# AJH_as3310_DUAL_ASR_02_4hp.net
KiCad netlist of a schematic drawn in EAGLE
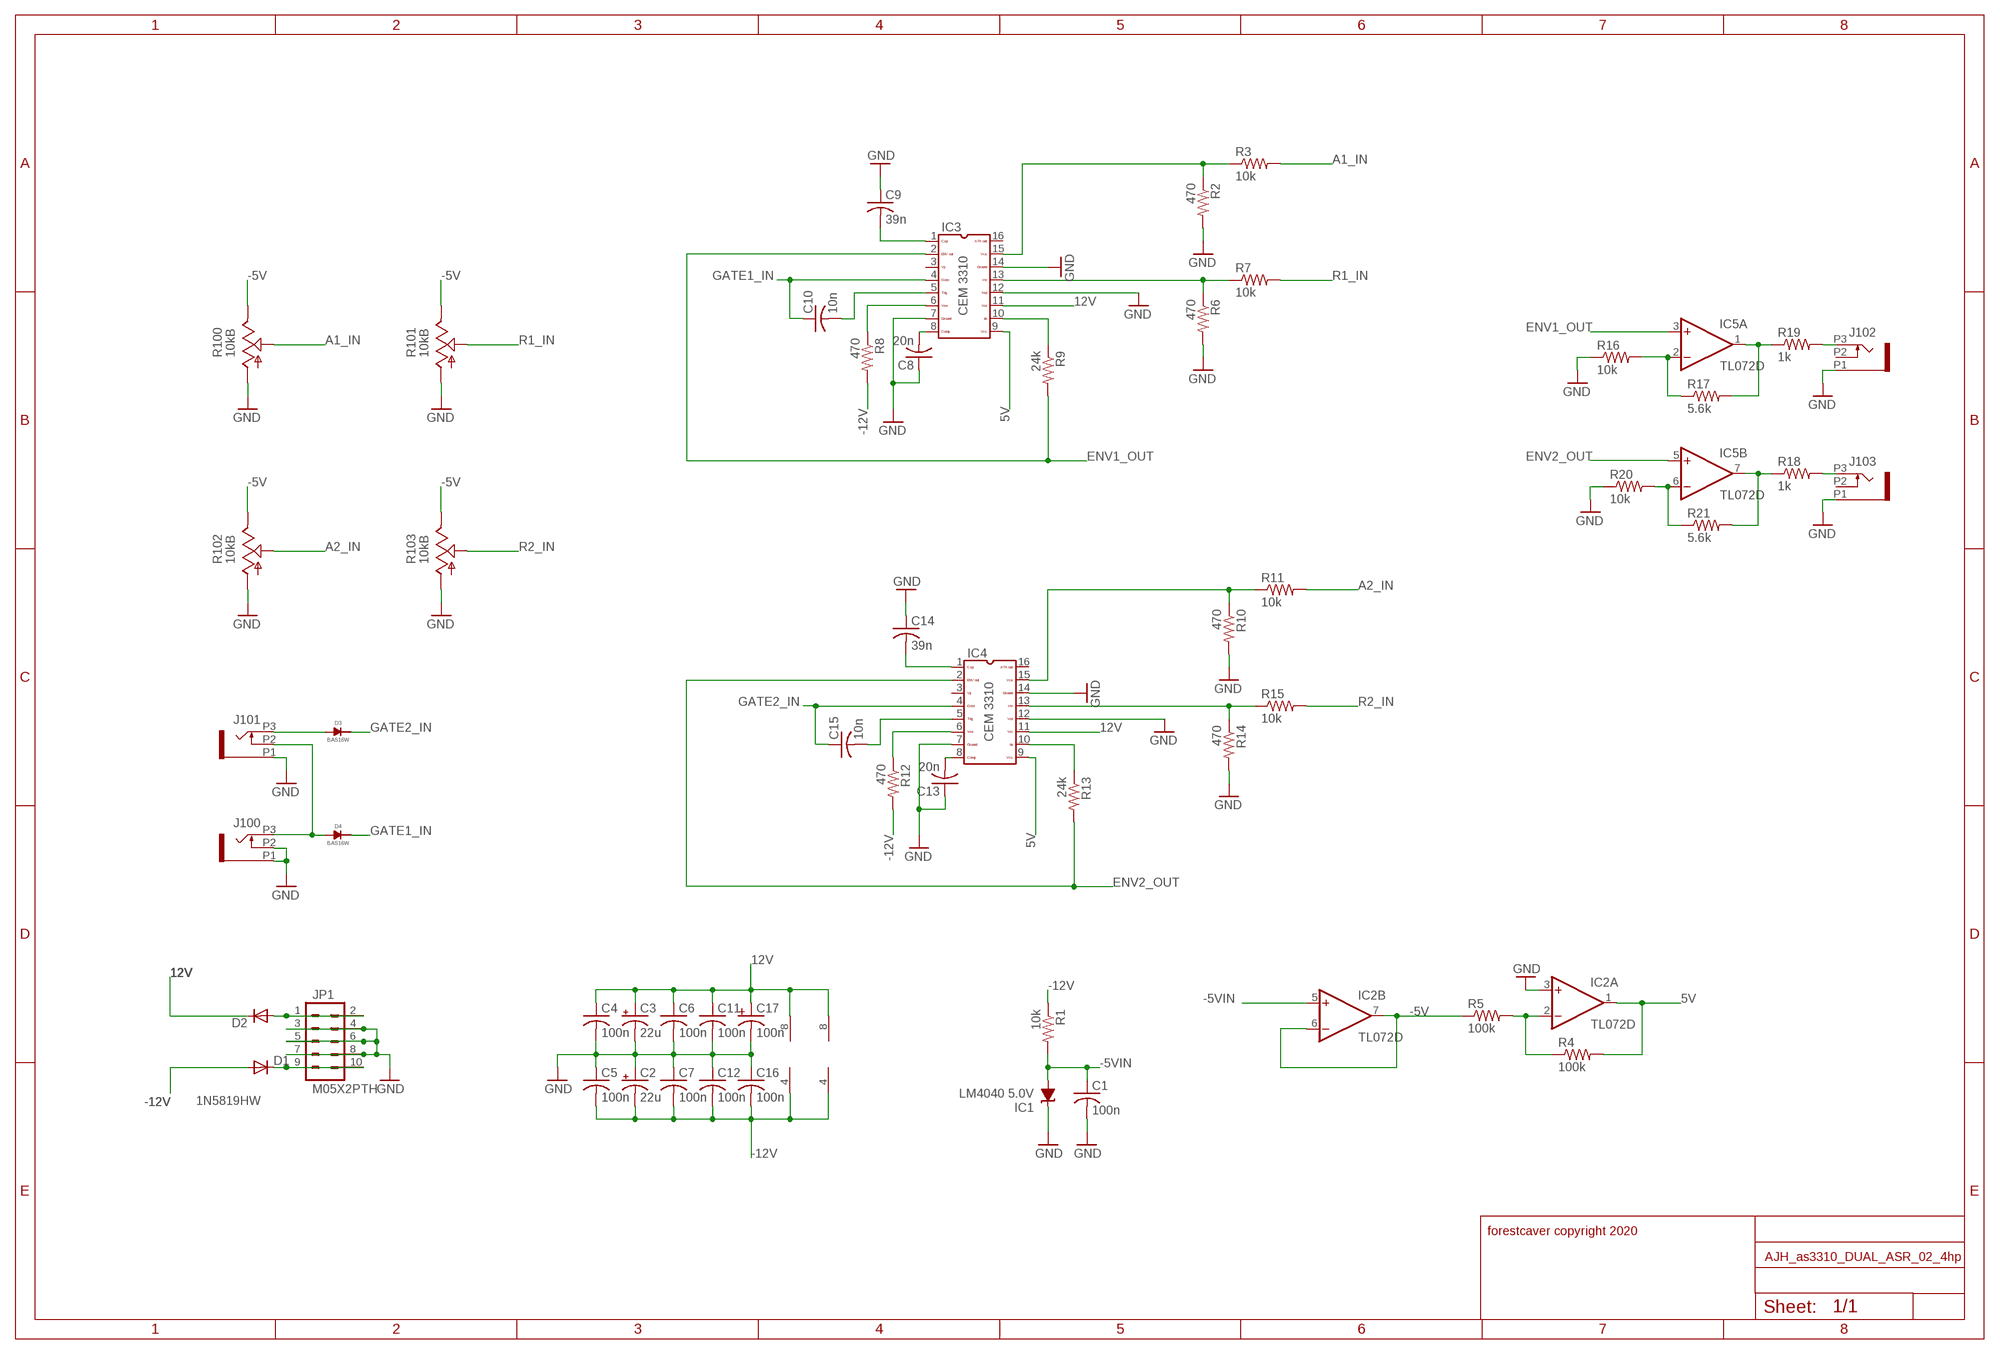
[diagram p0: schematic, sheet 1]

(export (version "E")
  (design (tool "Eeschema 10.0.6"))
  (components
    (comp (ref "C1")
      (value "100n")
      (footprint "eagle-import:C0603")
      (libsource (lib "eagle-import") (part "C-USC0603"))
    )
    (comp (ref "C2")
      (value "22u")
      (footprint "eagle-import:PANASONIC_B")
      (libsource (lib "eagle-import") (part "CPOL-USB"))
    )
    (comp (ref "C3")
      (value "22u")
      (footprint "eagle-import:PANASONIC_B")
      (libsource (lib "eagle-import") (part "CPOL-USB"))
    )
    (comp (ref "C4")
      (value "100n")
      (footprint "eagle-import:C0603")
      (libsource (lib "eagle-import") (part "C-USC0603"))
    )
    (comp (ref "C5")
      (value "100n")
      (footprint "eagle-import:C0603")
      (libsource (lib "eagle-import") (part "C-USC0603"))
    )
    (comp (ref "C6")
      (value "100n")
      (footprint "eagle-import:C0603")
      (libsource (lib "eagle-import") (part "C-USC0603"))
    )
    (comp (ref "C7")
      (value "100n")
      (footprint "eagle-import:C0603")
      (libsource (lib "eagle-import") (part "C-USC0603"))
    )
    (comp (ref "C8")
      (value "20n")
      (footprint "eagle-import:C0603")
      (libsource (lib "eagle-import") (part "C-USC0603"))
    )
    (comp (ref "C9")
      (value "39n")
      (footprint "eagle-import:C0603")
      (libsource (lib "eagle-import") (part "C-USC0603"))
    )
    (comp (ref "C10")
      (value "10n")
      (footprint "eagle-import:C0603")
      (libsource (lib "eagle-import") (part "C-USC0603"))
    )
    (comp (ref "C11")
      (value "100n")
      (footprint "eagle-import:C0603")
      (libsource (lib "eagle-import") (part "C-USC0603"))
    )
    (comp (ref "C12")
      (value "100n")
      (footprint "eagle-import:C0603")
      (libsource (lib "eagle-import") (part "C-USC0603"))
    )
    (comp (ref "C13")
      (value "20n")
      (footprint "eagle-import:C0603")
      (libsource (lib "eagle-import") (part "C-USC0603"))
    )
    (comp (ref "C14")
      (value "39n")
      (footprint "eagle-import:C0603")
      (libsource (lib "eagle-import") (part "C-USC0603"))
    )
    (comp (ref "C15")
      (value "10n")
      (footprint "eagle-import:C0603")
      (libsource (lib "eagle-import") (part "C-USC0603"))
    )
    (comp (ref "C16")
      (value "100n")
      (footprint "eagle-import:C0603")
      (libsource (lib "eagle-import") (part "C-USC0603"))
    )
    (comp (ref "C17")
      (value "100n")
      (footprint "eagle-import:C0603")
      (libsource (lib "eagle-import") (part "C-USC0603"))
    )
    (comp (ref "D1")
      (value "1N5819HW")
      (footprint "eagle-import:SOD123")
      (libsource (lib "eagle-import") (part "DIODE-SOD123"))
    )
    (comp (ref "D2")
      (value "1N5819HW")
      (footprint "eagle-import:SOD123")
      (libsource (lib "eagle-import") (part "DIODE-SOD123"))
    )
    (comp (ref "D3")
      (value "BAS16W")
      (footprint "eagle-import:SOT-323")
      (libsource (lib "eagle-import") (part "BAS16W"))
    )
    (comp (ref "D4")
      (value "BAS16W")
      (footprint "eagle-import:SOT-323")
      (libsource (lib "eagle-import") (part "BAS16W"))
    )
    (comp (ref "IC1")
      (value "LM4040 5.0V")
      (footprint "eagle-import:DBZ_R-PDSO-G3")
      (libsource (lib "eagle-import") (part "LM4041DBZC12"))
    )
    (comp (ref "IC2")
      (value "TL072D")
      (footprint "eagle-import:SO08")
      (libsource (lib "eagle-import") (part "TL072D"))
    )
    (comp (ref "IC3")
      (value "CEM3310SOIC16")
      (footprint "eagle-import:SO16")
      (libsource (lib "eagle-import") (part "CEM3310SOIC16"))
    )
    (comp (ref "IC4")
      (value "CEM3310SOIC16")
      (footprint "eagle-import:SO16")
      (libsource (lib "eagle-import") (part "CEM3310SOIC16"))
    )
    (comp (ref "IC5")
      (value "TL072D")
      (footprint "eagle-import:SO08")
      (libsource (lib "eagle-import") (part "TL072D"))
    )
    (comp (ref "J100")
      (value "PJ301_THONKICONN6")
      (footprint "eagle-import:WQP_PJ_301M6")
      (libsource (lib "eagle-import") (part "PJ301_THONKICONN6"))
    )
    (comp (ref "J101")
      (value "PJ301_THONKICONN6")
      (footprint "eagle-import:WQP_PJ_301M6")
      (libsource (lib "eagle-import") (part "PJ301_THONKICONN6"))
    )
    (comp (ref "J102")
      (value "PJ301_THONKICONN6")
      (footprint "eagle-import:WQP_PJ_301M6")
      (libsource (lib "eagle-import") (part "PJ301_THONKICONN6"))
    )
    (comp (ref "J103")
      (value "PJ301_THONKICONN6")
      (footprint "eagle-import:WQP_PJ_301M6")
      (libsource (lib "eagle-import") (part "PJ301_THONKICONN6"))
    )
    (comp (ref "JP1")
      (value "M05X2PTH")
      (footprint "eagle-import:AVR_ICSP")
      (libsource (lib "eagle-import") (part "M05X2PTH"))
    )
    (comp (ref "R1")
      (value "10k")
      (footprint "eagle-import:R0603")
      (libsource (lib "eagle-import") (part "R-US_R0603"))
    )
    (comp (ref "R2")
      (value "470")
      (footprint "eagle-import:R0603")
      (libsource (lib "eagle-import") (part "R-US_R0603"))
    )
    (comp (ref "R3")
      (value "10k")
      (footprint "eagle-import:R0603")
      (libsource (lib "eagle-import") (part "R-US_R0603"))
    )
    (comp (ref "R4")
      (value "100k")
      (footprint "eagle-import:R0603")
      (libsource (lib "eagle-import") (part "R-US_R0603"))
    )
    (comp (ref "R5")
      (value "100k")
      (footprint "eagle-import:R0603")
      (libsource (lib "eagle-import") (part "R-US_R0603"))
    )
    (comp (ref "R6")
      (value "470")
      (footprint "eagle-import:R0603")
      (libsource (lib "eagle-import") (part "R-US_R0603"))
    )
    (comp (ref "R7")
      (value "10k")
      (footprint "eagle-import:R0603")
      (libsource (lib "eagle-import") (part "R-US_R0603"))
    )
    (comp (ref "R8")
      (value "470")
      (footprint "eagle-import:R0603")
      (libsource (lib "eagle-import") (part "R-US_R0603"))
    )
    (comp (ref "R9")
      (value "24k")
      (footprint "eagle-import:R0603")
      (libsource (lib "eagle-import") (part "R-US_R0603"))
    )
    (comp (ref "R10")
      (value "470")
      (footprint "eagle-import:R0603")
      (libsource (lib "eagle-import") (part "R-US_R0603"))
    )
    (comp (ref "R11")
      (value "10k")
      (footprint "eagle-import:R0603")
      (libsource (lib "eagle-import") (part "R-US_R0603"))
    )
    (comp (ref "R12")
      (value "470")
      (footprint "eagle-import:R0603")
      (libsource (lib "eagle-import") (part "R-US_R0603"))
    )
    (comp (ref "R13")
      (value "24k")
      (footprint "eagle-import:R0603")
      (libsource (lib "eagle-import") (part "R-US_R0603"))
    )
    (comp (ref "R14")
      (value "470")
      (footprint "eagle-import:R0603")
      (libsource (lib "eagle-import") (part "R-US_R0603"))
    )
    (comp (ref "R15")
      (value "10k")
      (footprint "eagle-import:R0603")
      (libsource (lib "eagle-import") (part "R-US_R0603"))
    )
    (comp (ref "R16")
      (value "10k")
      (footprint "eagle-import:R0603")
      (libsource (lib "eagle-import") (part "R-US_R0603"))
    )
    (comp (ref "R17")
      (value "5.6k")
      (footprint "eagle-import:R0603")
      (libsource (lib "eagle-import") (part "R-US_R0603"))
    )
    (comp (ref "R18")
      (value "1k")
      (footprint "eagle-import:R0603")
      (libsource (lib "eagle-import") (part "R-US_R0603"))
    )
    (comp (ref "R19")
      (value "1k")
      (footprint "eagle-import:R0603")
      (libsource (lib "eagle-import") (part "R-US_R0603"))
    )
    (comp (ref "R20")
      (value "10k")
      (footprint "eagle-import:R0603")
      (libsource (lib "eagle-import") (part "R-US_R0603"))
    )
    (comp (ref "R21")
      (value "5.6k")
      (footprint "eagle-import:R0603")
      (libsource (lib "eagle-import") (part "R-US_R0603"))
    )
    (comp (ref "R100")
      (value "10kB")
      (footprint "eagle-import:ALPS_POT_VERTICAL")
      (libsource (lib "eagle-import") (part "POT_USVERTICAL"))
    )
    (comp (ref "R101")
      (value "10kB")
      (footprint "eagle-import:ALPS_POT_VERTICAL")
      (libsource (lib "eagle-import") (part "POT_USVERTICAL"))
    )
    (comp (ref "R102")
      (value "10kB")
      (footprint "eagle-import:ALPS_POT_VERTICAL")
      (libsource (lib "eagle-import") (part "POT_USVERTICAL"))
    )
    (comp (ref "R103")
      (value "10kB")
      (footprint "eagle-import:ALPS_POT_VERTICAL")
      (libsource (lib "eagle-import") (part "POT_USVERTICAL"))
    )
  )
  (nets
    (net (code "1") (name "/-5V") (class "Default")
      (node (ref "IC2") (pin "6") (pinfunction "-IN_6") (pintype "input"))
      (node (ref "IC2") (pin "7") (pinfunction "OUT_7") (pintype "output"))
      (node (ref "R100") (pin "P$1") (pinfunction "E_P$1") (pintype "passive"))
      (node (ref "R101") (pin "P$1") (pinfunction "E_P$1") (pintype "passive"))
      (node (ref "R102") (pin "P$1") (pinfunction "E_P$1") (pintype "passive"))
      (node (ref "R103") (pin "P$1") (pinfunction "E_P$1") (pintype "passive"))
      (node (ref "R5") (pin "1") (pinfunction "1_1") (pintype "passive"))
    )
    (net (code "2") (name "/-5VIN") (class "Default")
      (node (ref "C1") (pin "1") (pinfunction "1_1") (pintype "passive"))
      (node (ref "IC1") (pin "2") (pinfunction "A_2") (pintype "passive"))
      (node (ref "IC2") (pin "5") (pinfunction "+IN_5") (pintype "input"))
      (node (ref "R1") (pin "2") (pinfunction "2_2") (pintype "passive"))
    )
    (net (code "3") (name "/-12V") (class "Default")
      (node (ref "C12") (pin "2") (pinfunction "2_2") (pintype "passive"))
      (node (ref "C16") (pin "2") (pinfunction "2_2") (pintype "passive"))
      (node (ref "C2") (pin "-") (pinfunction "-_-") (pintype "passive"))
      (node (ref "C5") (pin "2") (pinfunction "2_2") (pintype "passive"))
      (node (ref "C7") (pin "2") (pinfunction "2_2") (pintype "passive"))
      (node (ref "D1") (pin "A") (pinfunction "A_A") (pintype "passive"))
      (node (ref "IC2") (pin "4") (pinfunction "V-_4") (pintype "power_in"))
      (node (ref "IC5") (pin "4") (pinfunction "V-_4") (pintype "power_in"))
      (node (ref "R1") (pin "1") (pinfunction "1_1") (pintype "passive"))
      (node (ref "R12") (pin "2") (pinfunction "2_2") (pintype "passive"))
      (node (ref "R8") (pin "2") (pinfunction "2_2") (pintype "passive"))
    )
    (net (code "4") (name "/5V") (class "Default")
      (node (ref "IC2") (pin "1") (pinfunction "OUT_1") (pintype "output"))
      (node (ref "IC3") (pin "9") (pinfunction "9_9") (pintype "power_in"))
      (node (ref "IC4") (pin "9") (pinfunction "9_9") (pintype "power_in"))
      (node (ref "R4") (pin "2") (pinfunction "2_2") (pintype "passive"))
    )
    (net (code "5") (name "/12V") (class "Default")
      (node (ref "C11") (pin "1") (pinfunction "1_1") (pintype "passive"))
      (node (ref "C17") (pin "1") (pinfunction "1_1") (pintype "passive"))
      (node (ref "C3") (pin "+") (pinfunction "+_+") (pintype "passive"))
      (node (ref "C4") (pin "1") (pinfunction "1_1") (pintype "passive"))
      (node (ref "C6") (pin "1") (pinfunction "1_1") (pintype "passive"))
      (node (ref "D2") (pin "C") (pinfunction "C_C") (pintype "passive"))
      (node (ref "IC2") (pin "8") (pinfunction "V+_8") (pintype "power_in"))
      (node (ref "IC3") (pin "11") (pinfunction "11_11") (pintype "power_in"))
      (node (ref "IC4") (pin "11") (pinfunction "11_11") (pintype "power_in"))
      (node (ref "IC5") (pin "8") (pinfunction "V+_8") (pintype "power_in"))
    )
    (net (code "6") (name "/A1_IN") (class "Default")
      (node (ref "R100") (pin "P$2") (pinfunction "S_P$2") (pintype "passive"))
      (node (ref "R3") (pin "2") (pinfunction "2_2") (pintype "passive"))
    )
    (net (code "7") (name "/A2_IN") (class "Default")
      (node (ref "R102") (pin "P$2") (pinfunction "S_P$2") (pintype "passive"))
      (node (ref "R11") (pin "2") (pinfunction "2_2") (pintype "passive"))
    )
    (net (code "8") (name "/ENV1_OUT") (class "Default")
      (node (ref "IC3") (pin "2") (pinfunction "2_2") (pintype "output"))
      (node (ref "IC5") (pin "3") (pinfunction "+IN_3") (pintype "input"))
      (node (ref "R9") (pin "2") (pinfunction "2_2") (pintype "passive"))
    )
    (net (code "9") (name "/ENV2_OUT") (class "Default")
      (node (ref "IC4") (pin "2") (pinfunction "2_2") (pintype "output"))
      (node (ref "IC5") (pin "5") (pinfunction "+IN_5") (pintype "input"))
      (node (ref "R13") (pin "2") (pinfunction "2_2") (pintype "passive"))
    )
    (net (code "10") (name "/GATE1_IN") (class "Default")
      (node (ref "C10") (pin "1") (pinfunction "1_1") (pintype "passive"))
      (node (ref "D4") (pin "CATHODE") (pinfunction "CATHODE_CATHODE") (pintype "bidirectional"))
      (node (ref "IC3") (pin "4") (pinfunction "4_4") (pintype "input"))
    )
    (net (code "11") (name "/GATE2_IN") (class "Default")
      (node (ref "C15") (pin "1") (pinfunction "1_1") (pintype "passive"))
      (node (ref "D3") (pin "CATHODE") (pinfunction "CATHODE_CATHODE") (pintype "bidirectional"))
      (node (ref "IC4") (pin "4") (pinfunction "4_4") (pintype "input"))
    )
    (net (code "12") (name "/R1_IN") (class "Default")
      (node (ref "R101") (pin "P$2") (pinfunction "S_P$2") (pintype "passive"))
      (node (ref "R7") (pin "2") (pinfunction "2_2") (pintype "passive"))
    )
    (net (code "13") (name "/R2_IN") (class "Default")
      (node (ref "R103") (pin "P$2") (pinfunction "S_P$2") (pintype "passive"))
      (node (ref "R15") (pin "2") (pinfunction "2_2") (pintype "passive"))
    )
    (net (code "14") (name "GND") (class "Default")
      (node (ref "C1") (pin "2") (pinfunction "2_2") (pintype "passive"))
      (node (ref "C11") (pin "2") (pinfunction "2_2") (pintype "passive"))
      (node (ref "C12") (pin "1") (pinfunction "1_1") (pintype "passive"))
      (node (ref "C13") (pin "1") (pinfunction "1_1") (pintype "passive"))
      (node (ref "C14") (pin "1") (pinfunction "1_1") (pintype "passive"))
      (node (ref "C16") (pin "1") (pinfunction "1_1") (pintype "passive"))
      (node (ref "C17") (pin "2") (pinfunction "2_2") (pintype "passive"))
      (node (ref "C2") (pin "+") (pinfunction "+_+") (pintype "passive"))
      (node (ref "C3") (pin "-") (pinfunction "-_-") (pintype "passive"))
      (node (ref "C4") (pin "2") (pinfunction "2_2") (pintype "passive"))
      (node (ref "C5") (pin "1") (pinfunction "1_1") (pintype "passive"))
      (node (ref "C6") (pin "2") (pinfunction "2_2") (pintype "passive"))
      (node (ref "C7") (pin "1") (pinfunction "1_1") (pintype "passive"))
      (node (ref "C8") (pin "1") (pinfunction "1_1") (pintype "passive"))
      (node (ref "C9") (pin "1") (pinfunction "1_1") (pintype "passive"))
      (node (ref "IC1") (pin "1") (pinfunction "C_1") (pintype "passive"))
      (node (ref "IC2") (pin "3") (pinfunction "+IN_3") (pintype "input"))
      (node (ref "IC3") (pin "12") (pinfunction "12_12") (pintype "power_in"))
      (node (ref "IC3") (pin "14") (pinfunction "14_14") (pintype "power_in"))
      (node (ref "IC3") (pin "7") (pinfunction "7_7") (pintype "power_in"))
      (node (ref "IC4") (pin "12") (pinfunction "12_12") (pintype "power_in"))
      (node (ref "IC4") (pin "14") (pinfunction "14_14") (pintype "power_in"))
      (node (ref "IC4") (pin "7") (pinfunction "7_7") (pintype "power_in"))
      (node (ref "J100") (pin "P1") (pinfunction "1_P1") (pintype "passive"))
      (node (ref "J100") (pin "P2") (pinfunction "2_P2") (pintype "passive"))
      (node (ref "J101") (pin "P1") (pinfunction "1_P1") (pintype "passive"))
      (node (ref "J102") (pin "P1") (pinfunction "1_P1") (pintype "passive"))
      (node (ref "J103") (pin "P1") (pinfunction "1_P1") (pintype "passive"))
      (node (ref "JP1") (pin "3") (pinfunction "3_3") (pintype "passive"))
      (node (ref "JP1") (pin "4") (pinfunction "4_4") (pintype "passive"))
      (node (ref "JP1") (pin "5") (pinfunction "5_5") (pintype "passive"))
      (node (ref "JP1") (pin "6") (pinfunction "6_6") (pintype "passive"))
      (node (ref "JP1") (pin "7") (pinfunction "7_7") (pintype "passive"))
      (node (ref "JP1") (pin "8") (pinfunction "8_8") (pintype "passive"))
      (node (ref "R10") (pin "2") (pinfunction "2_2") (pintype "passive"))
      (node (ref "R100") (pin "P$3") (pinfunction "A_P$3") (pintype "passive"))
      (node (ref "R101") (pin "P$3") (pinfunction "A_P$3") (pintype "passive"))
      (node (ref "R102") (pin "P$3") (pinfunction "A_P$3") (pintype "passive"))
      (node (ref "R103") (pin "P$3") (pinfunction "A_P$3") (pintype "passive"))
      (node (ref "R14") (pin "2") (pinfunction "2_2") (pintype "passive"))
      (node (ref "R16") (pin "1") (pinfunction "1_1") (pintype "passive"))
      (node (ref "R2") (pin "2") (pinfunction "2_2") (pintype "passive"))
      (node (ref "R20") (pin "1") (pinfunction "1_1") (pintype "passive"))
      (node (ref "R6") (pin "2") (pinfunction "2_2") (pintype "passive"))
    )
    (net (code "15") (name "Net-(C8-Pad2)") (class "Default")
      (node (ref "C8") (pin "2") (pinfunction "2_2") (pintype "passive"))
      (node (ref "IC3") (pin "8") (pinfunction "8_8") (pintype "bidirectional"))
    )
    (net (code "16") (name "Net-(C9-Pad2)") (class "Default")
      (node (ref "C9") (pin "2") (pinfunction "2_2") (pintype "passive"))
      (node (ref "IC3") (pin "1") (pinfunction "1_1") (pintype "bidirectional"))
    )
    (net (code "17") (name "Net-(C10-Pad2)") (class "Default")
      (node (ref "C10") (pin "2") (pinfunction "2_2") (pintype "passive"))
      (node (ref "IC3") (pin "5") (pinfunction "5_5") (pintype "input"))
    )
    (net (code "18") (name "Net-(C13-Pad2)") (class "Default")
      (node (ref "C13") (pin "2") (pinfunction "2_2") (pintype "passive"))
      (node (ref "IC4") (pin "8") (pinfunction "8_8") (pintype "bidirectional"))
    )
    (net (code "19") (name "Net-(C14-Pad2)") (class "Default")
      (node (ref "C14") (pin "2") (pinfunction "2_2") (pintype "passive"))
      (node (ref "IC4") (pin "1") (pinfunction "1_1") (pintype "bidirectional"))
    )
    (net (code "20") (name "Net-(C15-Pad2)") (class "Default")
      (node (ref "C15") (pin "2") (pinfunction "2_2") (pintype "passive"))
      (node (ref "IC4") (pin "5") (pinfunction "5_5") (pintype "input"))
    )
    (net (code "21") (name "Net-(D1-PadC)") (class "Default")
      (node (ref "D1") (pin "C") (pinfunction "C_C") (pintype "passive"))
      (node (ref "JP1") (pin "10") (pinfunction "10_10") (pintype "passive"))
      (node (ref "JP1") (pin "9") (pinfunction "9_9") (pintype "passive"))
    )
    (net (code "22") (name "Net-(D2-PadA)") (class "Default")
      (node (ref "D2") (pin "A") (pinfunction "A_A") (pintype "passive"))
      (node (ref "JP1") (pin "1") (pinfunction "1_1") (pintype "passive"))
      (node (ref "JP1") (pin "2") (pinfunction "2_2") (pintype "passive"))
    )
    (net (code "23") (name "Net-(IC2A--IN)") (class "Default")
      (node (ref "IC2") (pin "2") (pinfunction "-IN_2") (pintype "input"))
      (node (ref "R4") (pin "1") (pinfunction "1_1") (pintype "passive"))
      (node (ref "R5") (pin "2") (pinfunction "2_2") (pintype "passive"))
    )
    (net (code "24") (name "Net-(IC3-Pad6)") (class "Default")
      (node (ref "IC3") (pin "6") (pinfunction "6_6") (pintype "power_in"))
      (node (ref "R8") (pin "1") (pinfunction "1_1") (pintype "passive"))
    )
    (net (code "25") (name "Net-(IC3-Pad10)") (class "Default")
      (node (ref "IC3") (pin "10") (pinfunction "10_10") (pintype "power_in"))
      (node (ref "R9") (pin "1") (pinfunction "1_1") (pintype "passive"))
    )
    (net (code "26") (name "Net-(IC3-Pad13)") (class "Default")
      (node (ref "IC3") (pin "13") (pinfunction "13_13") (pintype "power_in"))
      (node (ref "R6") (pin "1") (pinfunction "1_1") (pintype "passive"))
      (node (ref "R7") (pin "1") (pinfunction "1_1") (pintype "passive"))
    )
    (net (code "27") (name "Net-(IC3-Pad15)") (class "Default")
      (node (ref "IC3") (pin "15") (pinfunction "15_15") (pintype "power_in"))
      (node (ref "R2") (pin "1") (pinfunction "1_1") (pintype "passive"))
      (node (ref "R3") (pin "1") (pinfunction "1_1") (pintype "passive"))
    )
    (net (code "28") (name "Net-(IC4-Pad6)") (class "Default")
      (node (ref "IC4") (pin "6") (pinfunction "6_6") (pintype "power_in"))
      (node (ref "R12") (pin "1") (pinfunction "1_1") (pintype "passive"))
    )
    (net (code "29") (name "Net-(IC4-Pad10)") (class "Default")
      (node (ref "IC4") (pin "10") (pinfunction "10_10") (pintype "power_in"))
      (node (ref "R13") (pin "1") (pinfunction "1_1") (pintype "passive"))
    )
    (net (code "30") (name "Net-(IC4-Pad13)") (class "Default")
      (node (ref "IC4") (pin "13") (pinfunction "13_13") (pintype "power_in"))
      (node (ref "R14") (pin "1") (pinfunction "1_1") (pintype "passive"))
      (node (ref "R15") (pin "1") (pinfunction "1_1") (pintype "passive"))
    )
    (net (code "31") (name "Net-(IC4-Pad15)") (class "Default")
      (node (ref "IC4") (pin "15") (pinfunction "15_15") (pintype "power_in"))
      (node (ref "R10") (pin "1") (pinfunction "1_1") (pintype "passive"))
      (node (ref "R11") (pin "1") (pinfunction "1_1") (pintype "passive"))
    )
    (net (code "32") (name "Net-(IC5A--IN)") (class "Default")
      (node (ref "IC5") (pin "2") (pinfunction "-IN_2") (pintype "input"))
      (node (ref "R16") (pin "2") (pinfunction "2_2") (pintype "passive"))
      (node (ref "R17") (pin "1") (pinfunction "1_1") (pintype "passive"))
    )
    (net (code "33") (name "Net-(IC5A-OUT)") (class "Default")
      (node (ref "IC5") (pin "1") (pinfunction "OUT_1") (pintype "output"))
      (node (ref "R17") (pin "2") (pinfunction "2_2") (pintype "passive"))
      (node (ref "R19") (pin "1") (pinfunction "1_1") (pintype "passive"))
    )
    (net (code "34") (name "Net-(IC5B--IN)") (class "Default")
      (node (ref "IC5") (pin "6") (pinfunction "-IN_6") (pintype "input"))
      (node (ref "R20") (pin "2") (pinfunction "2_2") (pintype "passive"))
      (node (ref "R21") (pin "1") (pinfunction "1_1") (pintype "passive"))
    )
    (net (code "35") (name "Net-(IC5B-OUT)") (class "Default")
      (node (ref "IC5") (pin "7") (pinfunction "OUT_7") (pintype "output"))
      (node (ref "R18") (pin "1") (pinfunction "1_1") (pintype "passive"))
      (node (ref "R21") (pin "2") (pinfunction "2_2") (pintype "passive"))
    )
    (net (code "36") (name "Net-(J100-3)") (class "Default")
      (node (ref "D4") (pin "ANODE") (pinfunction "ANODE_ANODE") (pintype "bidirectional"))
      (node (ref "J100") (pin "P3") (pinfunction "3_P3") (pintype "passive"))
      (node (ref "J101") (pin "P2") (pinfunction "2_P2") (pintype "passive"))
    )
    (net (code "37") (name "Net-(J101-3)") (class "Default")
      (node (ref "D3") (pin "ANODE") (pinfunction "ANODE_ANODE") (pintype "bidirectional"))
      (node (ref "J101") (pin "P3") (pinfunction "3_P3") (pintype "passive"))
    )
    (net (code "38") (name "Net-(J102-3)") (class "Default")
      (node (ref "J102") (pin "P3") (pinfunction "3_P3") (pintype "passive"))
      (node (ref "R19") (pin "2") (pinfunction "2_2") (pintype "passive"))
    )
    (net (code "39") (name "Net-(J103-3)") (class "Default")
      (node (ref "J103") (pin "P3") (pinfunction "3_P3") (pintype "passive"))
      (node (ref "R18") (pin "2") (pinfunction "2_2") (pintype "passive"))
    )
    (net (code "40") (name "unconnected-(IC3-Pad3)") (class "Default")
      (node (ref "IC3") (pin "3") (pinfunction "3_3") (pintype "bidirectional"))
    )
    (net (code "41") (name "unconnected-(IC3-Pad16)") (class "Default")
      (node (ref "IC3") (pin "16") (pinfunction "16_16") (pintype "output"))
    )
    (net (code "42") (name "unconnected-(IC4-Pad3)") (class "Default")
      (node (ref "IC4") (pin "3") (pinfunction "3_3") (pintype "bidirectional"))
    )
    (net (code "43") (name "unconnected-(IC4-Pad16)") (class "Default")
      (node (ref "IC4") (pin "16") (pinfunction "16_16") (pintype "output"))
    )
    (net (code "44") (name "unconnected-(J102-2-PadP2)") (class "Default")
      (node (ref "J102") (pin "P2") (pinfunction "2_P2") (pintype "passive"))
    )
    (net (code "45") (name "unconnected-(J103-2-PadP2)") (class "Default")
      (node (ref "J103") (pin "P2") (pinfunction "2_P2") (pintype "passive"))
    )
  )
)
